# 02-RaspberryPi_Header.net
KiCad netlist of a schematic drawn in Altium Designer
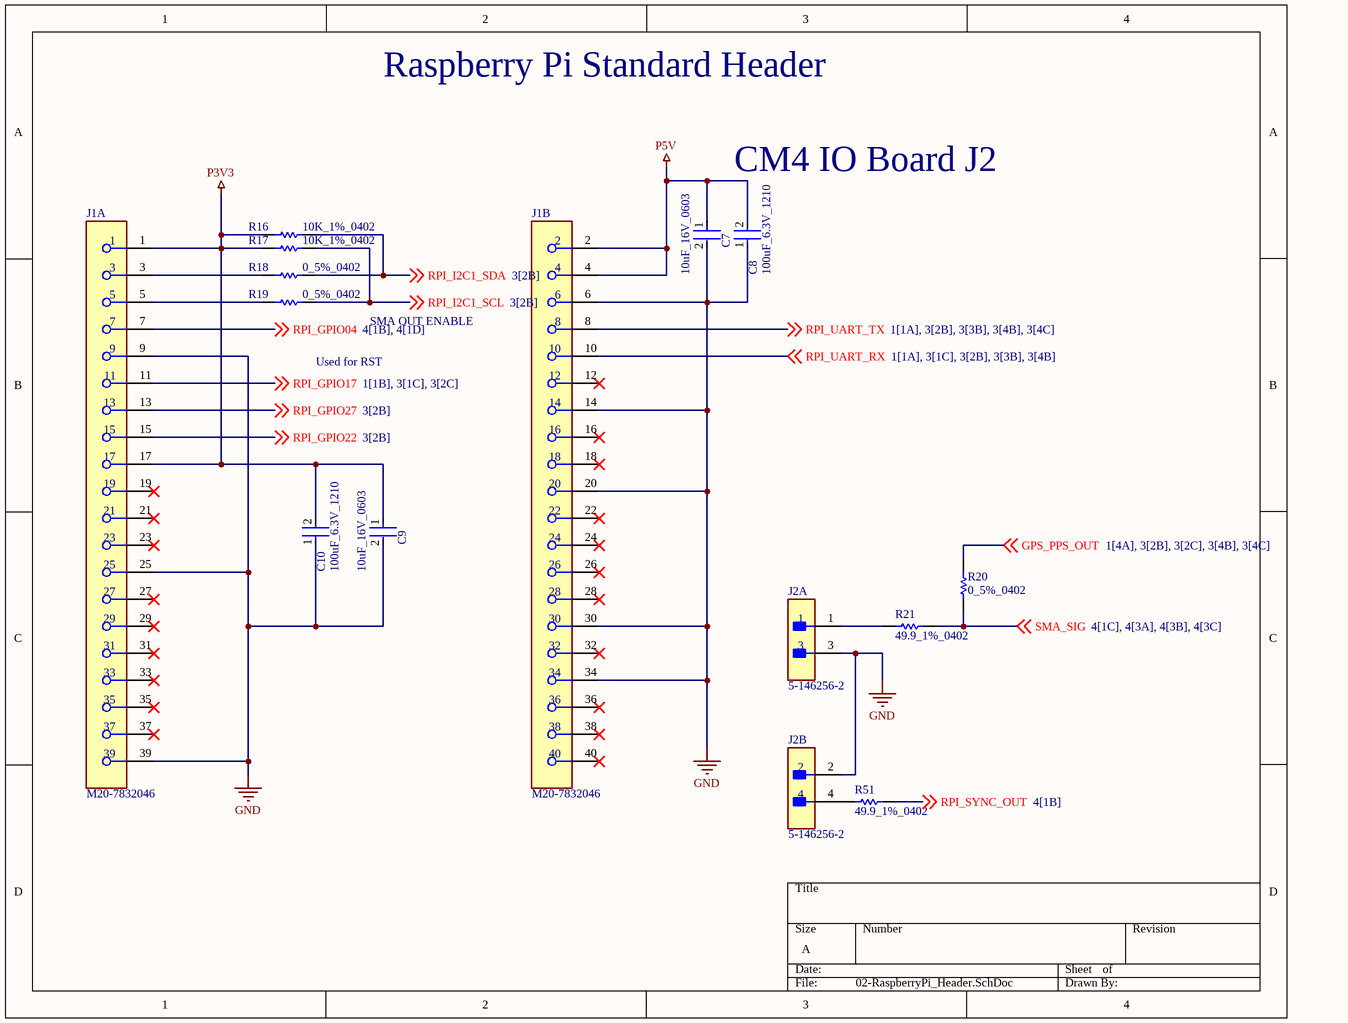
[diagram p0: 02-RaspberryPi_Header.SchDoc]

(export (version "E")
  (design (tool "Eeschema 10.0.6"))
  (components
    (comp (ref "C7")
      (value "10uF_16V_0603")
      (footprint "FP-0603-L_1_6_0_2-W_0_8_0-MFG")
      (description "Multilayer Ceramic Capacitor 10uF 16V X5R 20% SMD 0603 T/R")
      (fields (field (name "TOLERANCE") "20%"))
      (libsource (lib "Altium Content Vault") (part "b4654b650e69147ec39a6b967a45e02"))
    )
    (comp (ref "C8")
      (value "100uF_6.3V_1210")
      (footprint "FP-C1210C107M9PACTU-MFG")
      (description "CAP CER 100UF 6.3V X5R 1210")
      (fields (field (name "VOLTAGE") "6.3V") (field (name "TOLERANCE") "20%"))
      (libsource (lib "Altium Content Vault") (part "b4654b650e69147ec39a6b967a45e02"))
    )
    (comp (ref "C9")
      (value "10uF_16V_0603")
      (footprint "FP-0603-L_1_6_0_2-W_0_8_0-MFG")
      (description "Multilayer Ceramic Capacitor 10uF 16V X5R 20% SMD 0603 T/R")
      (fields (field (name "TOLERANCE") "20%"))
      (libsource (lib "Altium Content Vault") (part "b4654b650e69147ec39a6b967a45e02"))
    )
    (comp (ref "C10")
      (value "100uF_6.3V_1210")
      (footprint "FP-C1210C107M9PACTU-MFG")
      (description "CAP CER 100UF 6.3V X5R 1210")
      (fields (field (name "VOLTAGE") "6.3V") (field (name "TOLERANCE") "20%"))
      (libsource (lib "Altium Content Vault") (part "b4654b650e69147ec39a6b967a45e02"))
    )
    (comp (ref "J1")
      (value "M20-7832046")
      (footprint "FP-M20-7832046-MFG")
      (description "CONN RCPT 40POS 0.1 TIN PCB")
      (libsource (lib "Altium Content Vault") (part "e49c40d8a4b72700ef4f9e86232dadc"))
    )
    (comp (ref "J2")
      (value "5-146256-2")
      (footprint "FP-5-146256-2-MFG")
      (description "CONN HEADER VERT 4POS 2.54MM")
      (libsource (lib "Altium Content Vault") (part "1621473add15499e993d6bbd36d0f06"))
    )
    (comp (ref "R16")
      (value "10K_1%_0402")
      (footprint "RESC1005X40X25LL05T05")
      (description "Chip Resistor, 10 KOhm, +/- 1%, 0.1 W, -55 to 155 degC, 0402 (1005 Metric), RoHS, Tape and Reel")
      (fields (field (name "TOLERANCE") "1%") (field (name "MANUFACTURER") "Panasonic"))
      (libsource (lib "Altium Content Vault") (part "RES-2"))
    )
    (comp (ref "R17")
      (value "10K_1%_0402")
      (footprint "RESC1005X40X25LL05T05")
      (description "Chip Resistor, 10 KOhm, +/- 1%, 0.1 W, -55 to 155 degC, 0402 (1005 Metric), RoHS, Tape and Reel")
      (fields (field (name "TOLERANCE") "1%") (field (name "MANUFACTURER") "Panasonic"))
      (libsource (lib "Altium Content Vault") (part "RES-2"))
    )
    (comp (ref "R18")
      (value "0_5%_0402")
      (footprint "RESC1005X40X25NL05T10")
      (fields (field (name "MANUFACTURER") "Yageo / Phycomp") (field (name "PART NUMBER") "RC0402JR-070RL"))
      (libsource (lib "Altium Content Vault") (part "RES"))
    )
    (comp (ref "R19")
      (value "0_5%_0402")
      (footprint "RESC1005X40X25NL05T10")
      (fields (field (name "MANUFACTURER") "Yageo / Phycomp") (field (name "PART NUMBER") "RC0402JR-070RL"))
      (libsource (lib "Altium Content Vault") (part "RES"))
    )
    (comp (ref "R20")
      (value "0_5%_0402")
      (footprint "RESC1005X40X25NL05T10")
      (fields (field (name "MANUFACTURER") "Yageo / Phycomp") (field (name "PART NUMBER") "RC0402JR-070RL"))
      (libsource (lib "Altium Content Vault") (part "RES"))
    )
    (comp (ref "R21")
      (value "49.9_1%_0402")
      (footprint "RESC1005X40X25LL05T05")
      (fields (field (name "PART NUMBER") "CRCW040249K9FKED") (field (name "MANUFACTURER") "Vishay Dale"))
      (libsource (lib "Altium Content Vault") (part "RES"))
    )
    (comp (ref "R51")
      (value "49.9_1%_0402")
      (footprint "RESC1005X40X25LL05T05")
      (fields (field (name "PART NUMBER") "CRCW040249K9FKED") (field (name "MANUFACTURER") "Vishay Dale"))
      (libsource (lib "Altium Content Vault") (part "RES"))
    )
  )
  (nets
    (net (code "1") (name "GND") (class "Default")
      (node (ref "C10") (pin "1") (pinfunction "1_1") (pintype "passive"))
      (node (ref "C7") (pin "2") (pinfunction "2_2") (pintype "passive"))
      (node (ref "C8") (pin "1") (pinfunction "1_1") (pintype "passive"))
      (node (ref "C9") (pin "2") (pinfunction "2_2") (pintype "passive"))
      (node (ref "J1") (pin "14") (pinfunction "14_14") (pintype "passive"))
      (node (ref "J1") (pin "20") (pinfunction "20_20") (pintype "passive"))
      (node (ref "J1") (pin "25") (pinfunction "25_25") (pintype "passive"))
      (node (ref "J1") (pin "30") (pinfunction "30_30") (pintype "passive"))
      (node (ref "J1") (pin "34") (pinfunction "34_34") (pintype "passive"))
      (node (ref "J1") (pin "39") (pinfunction "39_39") (pintype "passive"))
      (node (ref "J1") (pin "6") (pinfunction "6_6") (pintype "passive"))
      (node (ref "J1") (pin "9") (pinfunction "9_9") (pintype "passive"))
      (node (ref "J2") (pin "2") (pinfunction "2_2") (pintype "passive"))
      (node (ref "J2") (pin "3") (pinfunction "3_3") (pintype "passive"))
    )
    (net (code "2") (name "GPS_PPS_OUT") (class "Default")
      (node (ref "R20") (pin "1") (pinfunction "1_1") (pintype "passive"))
    )
    (net (code "3") (name "Net-(J1-Pad3)") (class "Default")
      (node (ref "J1") (pin "3") (pinfunction "3_3") (pintype "passive"))
      (node (ref "R18") (pin "1") (pinfunction "1_1") (pintype "passive"))
    )
    (net (code "4") (name "Net-(J1-Pad5)") (class "Default")
      (node (ref "J1") (pin "5") (pinfunction "5_5") (pintype "passive"))
      (node (ref "R19") (pin "1") (pinfunction "1_1") (pintype "passive"))
    )
    (net (code "5") (name "Net-(J2-Pad1)") (class "Default")
      (node (ref "J2") (pin "1") (pinfunction "1_1") (pintype "passive"))
      (node (ref "R21") (pin "1") (pinfunction "1_1") (pintype "passive"))
    )
    (net (code "6") (name "Net-(J2-Pad4)") (class "Default")
      (node (ref "J2") (pin "4") (pinfunction "4_4") (pintype "passive"))
      (node (ref "R51") (pin "1") (pinfunction "1_1") (pintype "passive"))
    )
    (net (code "7") (name "P3V3") (class "Default")
      (node (ref "C10") (pin "2") (pinfunction "2_2") (pintype "passive"))
      (node (ref "C9") (pin "1") (pinfunction "1_1") (pintype "passive"))
      (node (ref "J1") (pin "1") (pinfunction "1_1") (pintype "passive"))
      (node (ref "J1") (pin "17") (pinfunction "17_17") (pintype "passive"))
      (node (ref "R16") (pin "1") (pinfunction "1_1") (pintype "passive"))
      (node (ref "R17") (pin "1") (pinfunction "1_1") (pintype "passive"))
    )
    (net (code "8") (name "P5V") (class "Default")
      (node (ref "C7") (pin "1") (pinfunction "1_1") (pintype "passive"))
      (node (ref "C8") (pin "2") (pinfunction "2_2") (pintype "passive"))
      (node (ref "J1") (pin "2") (pinfunction "2_2") (pintype "passive"))
      (node (ref "J1") (pin "4") (pinfunction "4_4") (pintype "passive"))
    )
    (net (code "9") (name "RPI_GPIO04") (class "Default")
      (node (ref "J1") (pin "7") (pinfunction "7_7") (pintype "passive"))
    )
    (net (code "10") (name "RPI_GPIO17") (class "Default")
      (node (ref "J1") (pin "11") (pinfunction "11_11") (pintype "passive"))
    )
    (net (code "11") (name "RPI_GPIO22") (class "Default")
      (node (ref "J1") (pin "15") (pinfunction "15_15") (pintype "passive"))
    )
    (net (code "12") (name "RPI_GPIO27") (class "Default")
      (node (ref "J1") (pin "13") (pinfunction "13_13") (pintype "passive"))
    )
    (net (code "13") (name "RPI_I2C1_SCL") (class "Default")
      (node (ref "R17") (pin "2") (pinfunction "2_2") (pintype "passive"))
      (node (ref "R19") (pin "2") (pinfunction "2_2") (pintype "passive"))
    )
    (net (code "14") (name "RPI_I2C1_SDA") (class "Default")
      (node (ref "R16") (pin "2") (pinfunction "2_2") (pintype "passive"))
      (node (ref "R18") (pin "2") (pinfunction "2_2") (pintype "passive"))
    )
    (net (code "15") (name "RPI_SYNC_OUT") (class "Default")
      (node (ref "R51") (pin "2") (pinfunction "2_2") (pintype "passive"))
    )
    (net (code "16") (name "RPI_UART_RX") (class "Default")
      (node (ref "J1") (pin "10") (pinfunction "10_10") (pintype "passive"))
    )
    (net (code "17") (name "RPI_UART_TX") (class "Default")
      (node (ref "J1") (pin "8") (pinfunction "8_8") (pintype "passive"))
    )
    (net (code "18") (name "SMA_SIG") (class "Default")
      (node (ref "R20") (pin "2") (pinfunction "2_2") (pintype "passive"))
      (node (ref "R21") (pin "2") (pinfunction "2_2") (pintype "passive"))
    )
    (net (code "19") (name "unconnected-(J1-Pad12)") (class "Default")
      (node (ref "J1") (pin "12") (pinfunction "12_12") (pintype "passive+no_connect"))
    )
    (net (code "20") (name "unconnected-(J1-Pad16)") (class "Default")
      (node (ref "J1") (pin "16") (pinfunction "16_16") (pintype "passive+no_connect"))
    )
    (net (code "21") (name "unconnected-(J1-Pad18)") (class "Default")
      (node (ref "J1") (pin "18") (pinfunction "18_18") (pintype "passive+no_connect"))
    )
    (net (code "22") (name "unconnected-(J1-Pad19)") (class "Default")
      (node (ref "J1") (pin "19") (pinfunction "19_19") (pintype "passive+no_connect"))
    )
    (net (code "23") (name "unconnected-(J1-Pad21)") (class "Default")
      (node (ref "J1") (pin "21") (pinfunction "21_21") (pintype "passive+no_connect"))
    )
    (net (code "24") (name "unconnected-(J1-Pad22)") (class "Default")
      (node (ref "J1") (pin "22") (pinfunction "22_22") (pintype "passive+no_connect"))
    )
    (net (code "25") (name "unconnected-(J1-Pad23)") (class "Default")
      (node (ref "J1") (pin "23") (pinfunction "23_23") (pintype "passive+no_connect"))
    )
    (net (code "26") (name "unconnected-(J1-Pad24)") (class "Default")
      (node (ref "J1") (pin "24") (pinfunction "24_24") (pintype "passive+no_connect"))
    )
    (net (code "27") (name "unconnected-(J1-Pad26)") (class "Default")
      (node (ref "J1") (pin "26") (pinfunction "26_26") (pintype "passive+no_connect"))
    )
    (net (code "28") (name "unconnected-(J1-Pad27)") (class "Default")
      (node (ref "J1") (pin "27") (pinfunction "27_27") (pintype "passive+no_connect"))
    )
    (net (code "29") (name "unconnected-(J1-Pad28)") (class "Default")
      (node (ref "J1") (pin "28") (pinfunction "28_28") (pintype "passive+no_connect"))
    )
    (net (code "30") (name "unconnected-(J1-Pad29)") (class "Default")
      (node (ref "J1") (pin "29") (pinfunction "29_29") (pintype "passive+no_connect"))
    )
    (net (code "31") (name "unconnected-(J1-Pad31)") (class "Default")
      (node (ref "J1") (pin "31") (pinfunction "31_31") (pintype "passive+no_connect"))
    )
    (net (code "32") (name "unconnected-(J1-Pad32)") (class "Default")
      (node (ref "J1") (pin "32") (pinfunction "32_32") (pintype "passive+no_connect"))
    )
    (net (code "33") (name "unconnected-(J1-Pad33)") (class "Default")
      (node (ref "J1") (pin "33") (pinfunction "33_33") (pintype "passive+no_connect"))
    )
    (net (code "34") (name "unconnected-(J1-Pad35)") (class "Default")
      (node (ref "J1") (pin "35") (pinfunction "35_35") (pintype "passive+no_connect"))
    )
    (net (code "35") (name "unconnected-(J1-Pad36)") (class "Default")
      (node (ref "J1") (pin "36") (pinfunction "36_36") (pintype "passive+no_connect"))
    )
    (net (code "36") (name "unconnected-(J1-Pad37)") (class "Default")
      (node (ref "J1") (pin "37") (pinfunction "37_37") (pintype "passive+no_connect"))
    )
    (net (code "37") (name "unconnected-(J1-Pad38)") (class "Default")
      (node (ref "J1") (pin "38") (pinfunction "38_38") (pintype "passive+no_connect"))
    )
    (net (code "38") (name "unconnected-(J1-Pad40)") (class "Default")
      (node (ref "J1") (pin "40") (pinfunction "40_40") (pintype "passive+no_connect"))
    )
  )
)
